# FontesLineares.net
KiCad netlist of a schematic drawn in Altium Designer
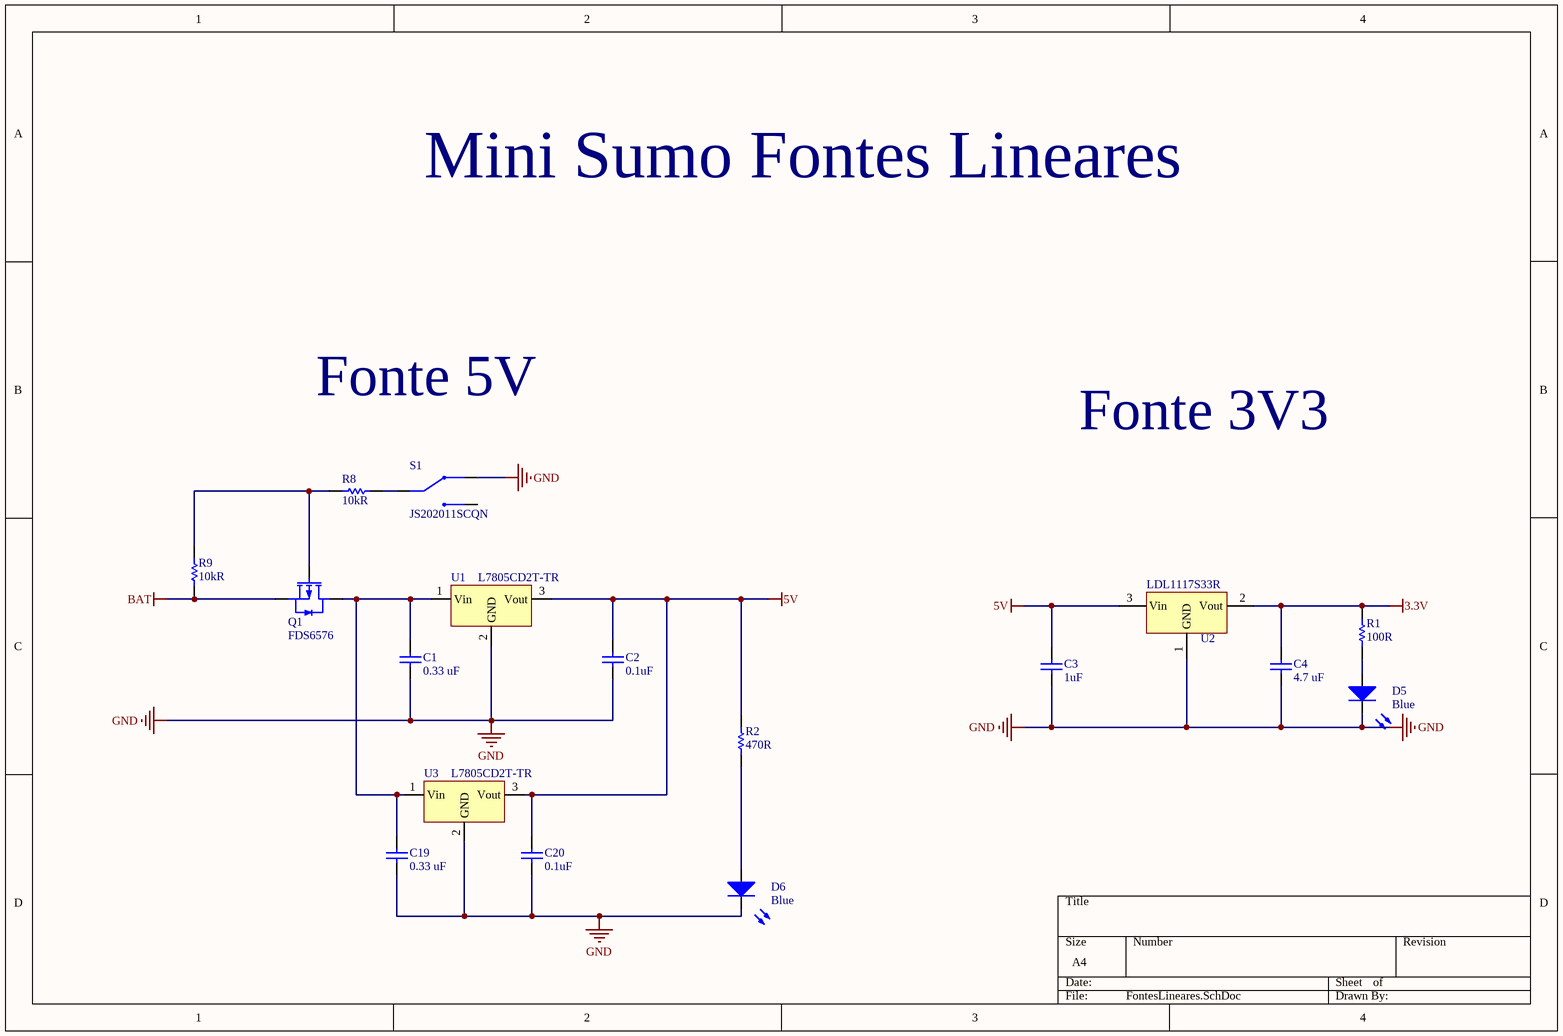
[diagram p0: FontesLineares.SchDoc]

(export (version "E")
  (design (tool "Eeschema 10.0.6"))
  (components
    (comp (ref "C1")
      (value "0.33 uF")
      (footprint "C0805")
      (description "CAP CER 0.33UF 25V X7R 0805")
      (fields
        (field (name "MANUFACTURER") "Murata Eletronics")
        (field (name "PART NUMBER") "GCM21BR71E334KA37K")
        (field (name "LIBRARY CONTROL - PERSON THAT CHECKED FOOTPRINT") "Nikaum")
        (field (name "LIBRARY CONTROL - PERSON THAT CHECKED SCHEMATIC") "Nikaum")
        (field (name "LIBRARY CONTROL - PERSON THAT DID THE LAST UPDATE FOOTPRINT") "Nikaum")
        (field (name "LIBRARY CONTROL - PERSON THAT DID THE LAST UPDATE SCHEMATIC") "Nikaum")
      )
      (libsource (lib "Uai!Tecas") (part "GCM21BR71E334KA37K"))
    )
    (comp (ref "C2")
      (value "0.1uF")
      (footprint "C0805")
      (description "CAP CER 0.1uF 25V X7R 0805")
      (fields
        (field (name "MANUFACTURER") "Kemet")
        (field (name "PART NUMBER") "C0805C104M3RACTU")
        (field (name "LIBRARY CONTROL - PERSON THAT CHECKED SCHEMATIC") "Guilherme")
        (field (name "LIBRARY CONTROL - PERSON THAT DID THE LAST UPDATE SCHEMATIC") "Marcos")
      )
      (libsource (lib "Uai!Tecas") (part "C0805C104M3RACTU"))
    )
    (comp (ref "C3")
      (value "1uF")
      (footprint "C0603")
      (description "CAP CER 1UF 25V X7R 0603")
      (libsource (lib "Uai!Tecas") (part "Capacitor Model"))
    )
    (comp (ref "C4")
      (value "4.7 uF")
      (footprint "C0805")
      (description "CAP CER 4.7uF 25V X5R 0805")
      (fields
        (field (name "MANUFACTURER") "MURATA ELECTRONICS")
        (field (name "PART NUMBER") "GRM219R61E475KA73D")
        (field (name "LIBRARY CONTROL - PERSON THAT CHECKED FOOTPRINT") "Cage")
        (field (name "LIBRARY CONTROL - PERSON THAT CHECKED SCHEMATIC") "Cage")
        (field (name "LIBRARY CONTROL - PERSON THAT DID THE LAST UPDATE FOOTPRINT") "Cage")
        (field (name "LIBRARY CONTROL - PERSON THAT DID THE LAST UPDATE SCHEMATIC") "Cage")
      )
      (libsource (lib "Uai!Tecas") (part "GRM219R61E475KA73D"))
    )
    (comp (ref "C19")
      (value "0.33 uF")
      (footprint "C0805")
      (description "CAP CER 0.33UF 25V X7R 0805")
      (fields
        (field (name "MANUFACTURER") "Murata Eletronics")
        (field (name "PART NUMBER") "GCM21BR71E334KA37K")
        (field (name "LIBRARY CONTROL - PERSON THAT CHECKED FOOTPRINT") "Nikaum")
        (field (name "LIBRARY CONTROL - PERSON THAT CHECKED SCHEMATIC") "Nikaum")
        (field (name "LIBRARY CONTROL - PERSON THAT DID THE LAST UPDATE FOOTPRINT") "Nikaum")
        (field (name "LIBRARY CONTROL - PERSON THAT DID THE LAST UPDATE SCHEMATIC") "Nikaum")
      )
      (libsource (lib "Uai!Tecas") (part "GCM21BR71E334KA37K"))
    )
    (comp (ref "C20")
      (value "0.1uF")
      (footprint "C0805")
      (description "CAP CER 0.1uF 25V X7R 0805")
      (fields
        (field (name "MANUFACTURER") "Kemet")
        (field (name "PART NUMBER") "C0805C104M3RACTU")
        (field (name "LIBRARY CONTROL - PERSON THAT CHECKED SCHEMATIC") "Guilherme")
        (field (name "LIBRARY CONTROL - PERSON THAT DID THE LAST UPDATE SCHEMATIC") "Marcos")
      )
      (libsource (lib "Uai!Tecas") (part "C0805C104M3RACTU"))
    )
    (comp (ref "D5")
      (value "Blue")
      (footprint "DIODO_2-SMD-3215")
      (description "LED 75mW BLUE 45MCD 3215")
      (fields
        (field (name "MANUFACTURER") "Everlight Electronics")
        (field (name "PART NUMBER") "EAST3215BA5")
        (field (name "LIBRARY CONTROL - PERSON THAT CHECKED FOOTPRINT") "Lucas")
        (field (name "LIBRARY CONTROL - PERSON THAT CHECKED SCHEMATIC") "Lucas")
        (field (name "LIBRARY CONTROL - PERSON THAT DID THE LAST UPDATE FOOTPRINT") "Stéfany (Ster)")
        (field (name "LIBRARY CONTROL - PERSON THAT DID THE LAST UPDATE SCHEMATIC") "Stéfany (Ster)")
      )
      (libsource (lib "Diodo") (part "EAST3215BA5"))
    )
    (comp (ref "D6")
      (value "Blue")
      (footprint "DIODO_2-SMD-3215")
      (description "LED 75mW BLUE 45MCD 3215")
      (fields
        (field (name "MANUFACTURER") "Everlight Electronics")
        (field (name "PART NUMBER") "EAST3215BA5")
        (field (name "LIBRARY CONTROL - PERSON THAT CHECKED FOOTPRINT") "Lucas")
        (field (name "LIBRARY CONTROL - PERSON THAT CHECKED SCHEMATIC") "Lucas")
        (field (name "LIBRARY CONTROL - PERSON THAT DID THE LAST UPDATE FOOTPRINT") "Stéfany (Ster)")
        (field (name "LIBRARY CONTROL - PERSON THAT DID THE LAST UPDATE SCHEMATIC") "Stéfany (Ster)")
      )
      (libsource (lib "Diodo") (part "EAST3215BA5"))
    )
    (comp (ref "Q1")
      (value "FDS6576")
      (footprint "SOIC-8")
      (description "MOSFET P-CH 20V 11A SOIC-8")
      (fields (field (name "PART NUMBER") "SOIC-8") (field (name "MANUFACTURER") "onsemi / Fairchild"))
      (libsource (lib "Uai!Tecas") (part "FDS6576"))
    )
    (comp (ref "R1")
      (value "100R")
      (footprint "RESISTOR_0805")
      (description "RES SMD 100 OHM 1% 1/8W 0805")
      (fields
        (field (name "MANUFACTURER") "Vishay / Dale")
        (field (name "PART NUMBER") "CRCW0805100RFKEA")
        (field (name "LIBRARY CONTROL - PERSON THAT CHECKED SCHEMATIC") "Marcos")
        (field (name "LIBRARY CONTROL - PERSON THAT DID THE LAST UPDATE FOOTPRINT") "Dalarme")
        (field (name "LIBRARY CONTROL - PERSON THAT DID THE LAST UPDATE SCHEMATIC") "Marcos")
      )
      (libsource (lib "Uai!Tecas") (part "CRCW0805100RFKEA"))
    )
    (comp (ref "R2")
      (value "470R")
      (footprint "RESISTOR_0805")
      (description "RES SMD 470 OHM 5% 1/8W 0805")
      (fields
        (field (name "MANUFACTURER") "Panasonic")
        (field (name "PART NUMBER") "667-ERJ-6GEYJ471V")
        (field (name "LIBRARY CONTROL - PERSON THAT CHECKED SCHEMATIC") "Marcos")
        (field (name "LIBRARY CONTROL - PERSON THAT DID THE LAST UPDATE FOOTPRINT") "Dalarme")
        (field (name "LIBRARY CONTROL - PERSON THAT DID THE LAST UPDATE SCHEMATIC") "Marcos")
      )
      (libsource (lib "Uai!Tecas") (part "ERJ-6GEYJ471V"))
    )
    (comp (ref "R8")
      (value "10kR")
      (footprint "RESISTOR_0603")
      (description "RES SMD 10K OHM 5% 1/10W 0603")
      (fields
        (field (name "MANUFACTURER") "Yageo")
        (field (name "PART NUMBER") "RC0603JR-0710KL")
        (field (name "LIBRARY CONTROL - PERSON THAT CHECKED SCHEMATIC") "Marcos")
        (field (name "LIBRARY CONTROL - PERSON THAT DID THE LAST UPDATE FOOTPRINT") "Dalarme")
        (field (name "LIBRARY CONTROL - PERSON THAT DID THE LAST UPDATE SCHEMATIC") "Marcos")
      )
      (libsource (lib "Uai!Tecas") (part "RC0603JR-0710KL"))
    )
    (comp (ref "R9")
      (value "10kR")
      (footprint "RESISTOR_0603")
      (description "RES SMD 10K OHM 5% 1/10W 0603")
      (fields
        (field (name "MANUFACTURER") "Yageo")
        (field (name "PART NUMBER") "RC0603JR-0710KL")
        (field (name "LIBRARY CONTROL - PERSON THAT CHECKED SCHEMATIC") "Marcos")
        (field (name "LIBRARY CONTROL - PERSON THAT DID THE LAST UPDATE FOOTPRINT") "Dalarme")
        (field (name "LIBRARY CONTROL - PERSON THAT DID THE LAST UPDATE SCHEMATIC") "Marcos")
      )
      (libsource (lib "Uai!Tecas") (part "RC0603JR-0710KL"))
    )
    (comp (ref "S1")
      (value "JS202011SCQN")
      (footprint "DPDT")
      (description "DEEP SWITCH 4 POSITIONS")
      (fields
        (field (name "MANUFACTURER") "C&K")
        (field (name "MOUSER PART NUMBER") "611-JS202011SCQN")
        (field (name "LIBRARY CONTROL - PERSON THAT CHECKED FOOTPRINT") "Nikaum")
        (field (name "LIBRARY CONTROL - PERSON THAT CHECKED SCHEMATIC") "Nikaum")
        (field (name "LIBRARY CONTROL - PERSON THAT DID THE LAST UPDATE FOOTPRINT") "Nikaum")
        (field (name "LIBRARY CONTROL - PERSON THAT DID THE LAST UPDATE SCHEMATIC") "Nikaum")
      )
      (libsource (lib "Diversos") (part "JS202011SCQN"))
    )
    (comp (ref "U1")
      (value "L7805CD2T-TR")
      (footprint "D2PAK")
      (description "IC REG LINEAR 5V 1A D2PAK")
      (fields
        (field (name "MANUFACTURER") "ST")
        (field (name "LIBRARY CONTROL - PERSON THAT CHECKED FOOTPRINT") "Nícolas")
        (field (name "LIBRARY CONTROL - PERSON THAT CHECKED SCHEMATIC") "Nícolas")
        (field (name "LIBRARY CONTROL - PERSON THAT DID THE LAST UPDATE SCHEMATIC") "Nícolas")
      )
      (libsource (lib "Uai!Tecas") (part "L7805CD2T-TR"))
    )
    (comp (ref "U2")
      (value "LDL1117S33R")
      (footprint "SOT-223-4")
      (description "IC REG LINEAR 3.3V 1.2A SOT-223-4")
      (fields
        (field (name "MANUFACTURER") "STMicroelectronics")
        (field (name "LIBRARY CONTROL - PERSON THAT CHECKED FOOTPRINT") "Nícolas")
        (field (name "LIBRARY CONTROL - PERSON THAT CHECKED SCHEMATIC") "Nícolas")
        (field (name "LIBRARY CONTROL - PERSON THAT DID THE LAST UPDATE FOOTPRINT") "Pierre")
        (field (name "LIBRARY CONTROL - PERSON THAT DID THE LAST UPDATE SCHEMATIC") "Nícolas")
      )
      (libsource (lib "Uai!Tecas") (part "LDL1117S33R"))
    )
    (comp (ref "U3")
      (value "L7805CD2T-TR")
      (footprint "D2PAK")
      (description "IC REG LINEAR 5V 1A D2PAK")
      (fields
        (field (name "MANUFACTURER") "ST")
        (field (name "LIBRARY CONTROL - PERSON THAT CHECKED FOOTPRINT") "Nícolas")
        (field (name "LIBRARY CONTROL - PERSON THAT CHECKED SCHEMATIC") "Nícolas")
        (field (name "LIBRARY CONTROL - PERSON THAT DID THE LAST UPDATE SCHEMATIC") "Nícolas")
      )
      (libsource (lib "Uai!Tecas") (part "L7805CD2T-TR"))
    )
  )
  (nets
    (net (code "1") (name "3.3V") (class "Default")
      (node (ref "C4") (pin "2") (pinfunction "2_2") (pintype "passive"))
      (node (ref "R1") (pin "2") (pinfunction "2_2") (pintype "passive"))
      (node (ref "U2") (pin "2") (pinfunction "Vout_2") (pintype "power_in"))
    )
    (net (code "2") (name "5V") (class "Default")
      (node (ref "C2") (pin "2") (pinfunction "2_2") (pintype "passive"))
      (node (ref "C20") (pin "2") (pinfunction "2_2") (pintype "passive"))
      (node (ref "C3") (pin "2") (pinfunction "2_2") (pintype "passive"))
      (node (ref "R2") (pin "2") (pinfunction "2_2") (pintype "passive"))
      (node (ref "U1") (pin "3") (pinfunction "Vout_3") (pintype "power_in"))
      (node (ref "U2") (pin "3") (pinfunction "Vin_3") (pintype "power_in"))
      (node (ref "U3") (pin "3") (pinfunction "Vout_3") (pintype "power_in"))
    )
    (net (code "3") (name "BAT") (class "Default")
      (node (ref "Q1") (pin "S") (pinfunction "S_S") (pintype "passive"))
      (node (ref "R9") (pin "1") (pinfunction "1_1") (pintype "passive"))
    )
    (net (code "4") (name "GND") (class "Default")
      (node (ref "C1") (pin "1") (pinfunction "1_1") (pintype "passive"))
      (node (ref "C19") (pin "1") (pinfunction "1_1") (pintype "passive"))
      (node (ref "C2") (pin "1") (pinfunction "1_1") (pintype "passive"))
      (node (ref "C20") (pin "1") (pinfunction "1_1") (pintype "passive"))
      (node (ref "C3") (pin "1") (pinfunction "1_1") (pintype "passive"))
      (node (ref "C4") (pin "1") (pinfunction "1_1") (pintype "passive"))
      (node (ref "D5") (pin "C") (pinfunction "C_C") (pintype "passive"))
      (node (ref "D6") (pin "C") (pinfunction "C_C") (pintype "passive"))
      (node (ref "S1") (pin "A2") (pinfunction "4_A2") (pintype "passive"))
      (node (ref "U1") (pin "2") (pinfunction "GND_2") (pintype "power_in"))
      (node (ref "U2") (pin "1") (pinfunction "GND_1") (pintype "power_in"))
      (node (ref "U3") (pin "2") (pinfunction "GND_2") (pintype "power_in"))
    )
    (net (code "5") (name "Net-(D5-PadA)") (class "Default")
      (node (ref "D5") (pin "A") (pinfunction "A_A") (pintype "passive"))
      (node (ref "R1") (pin "1") (pinfunction "1_1") (pintype "passive"))
    )
    (net (code "6") (name "Net-(D6-PadA)") (class "Default")
      (node (ref "D6") (pin "A") (pinfunction "A_A") (pintype "passive"))
      (node (ref "R2") (pin "1") (pinfunction "1_1") (pintype "passive"))
    )
    (net (code "7") (name "Net-(Q1-PadG)") (class "Default")
      (node (ref "Q1") (pin "G") (pinfunction "G_G") (pintype "passive"))
      (node (ref "R8") (pin "2") (pinfunction "2_2") (pintype "passive"))
      (node (ref "R9") (pin "2") (pinfunction "2_2") (pintype "passive"))
    )
    (net (code "8") (name "Net-(S1-1)") (class "Default")
      (node (ref "R8") (pin "1") (pinfunction "1_1") (pintype "passive"))
      (node (ref "S1") (pin "A1") (pinfunction "1_A1") (pintype "passive"))
    )
    (net (code "9") (name "Net-(U1-Vin)") (class "Default")
      (node (ref "C1") (pin "2") (pinfunction "2_2") (pintype "passive"))
      (node (ref "C19") (pin "2") (pinfunction "2_2") (pintype "passive"))
      (node (ref "Q1") (pin "D") (pinfunction "D_D") (pintype "passive"))
      (node (ref "U1") (pin "1") (pinfunction "Vin_1") (pintype "power_in"))
      (node (ref "U3") (pin "1") (pinfunction "Vin_1") (pintype "power_in"))
    )
    (net (code "10") (name "unconnected-(S1-3-PadA3)") (class "Default")
      (node (ref "S1") (pin "A3") (pinfunction "3_A3") (pintype "passive"))
    )
  )
)
